# SW102_nRF51x22.net
KiCad netlist of a schematic drawn in EAGLE
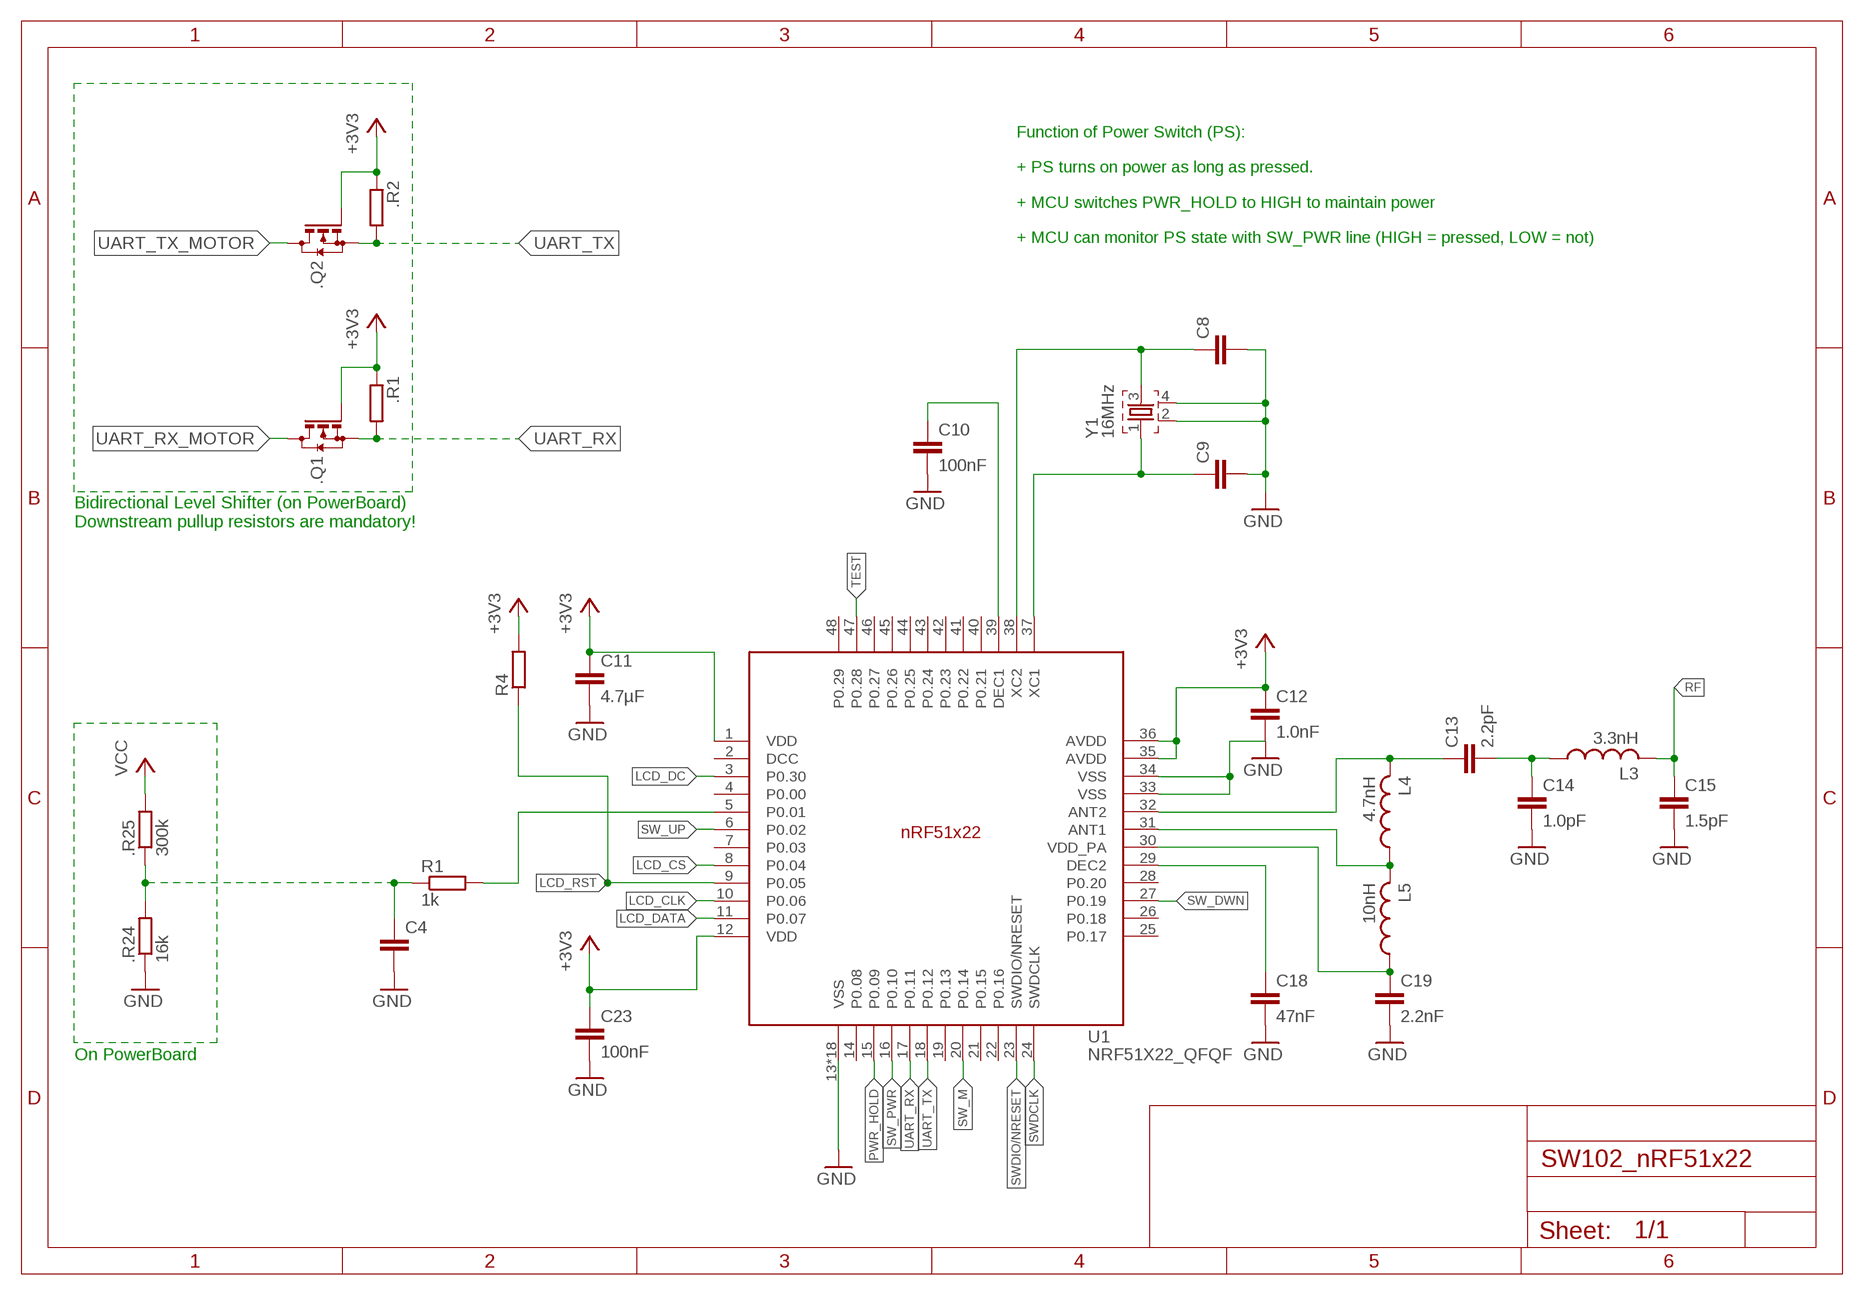
[diagram p0: schematic, sheet 1]

(export (version "E")
  (design (tool "Eeschema 10.0.6"))
  (components
    (comp (ref ".Q1")
      (value "BSS123")
      (footprint "eagle-import:SOT23")
      (libsource (lib "eagle-import") (part "BSS123"))
    )
    (comp (ref ".Q2")
      (value "BSS123")
      (footprint "eagle-import:SOT23")
      (libsource (lib "eagle-import") (part "BSS123"))
    )
    (comp (ref ".R1")
      (value "R-EU_R0603")
      (footprint "eagle-import:R0603")
      (libsource (lib "eagle-import") (part "R-EU_R0603"))
    )
    (comp (ref ".R2")
      (value "R-EU_R0603")
      (footprint "eagle-import:R0603")
      (libsource (lib "eagle-import") (part "R-EU_R0603"))
    )
    (comp (ref ".R24")
      (value "16k")
      (footprint "eagle-import:R0603")
      (libsource (lib "eagle-import") (part "R-EU_R0603"))
    )
    (comp (ref ".R25")
      (value "300k")
      (footprint "eagle-import:R0603")
      (libsource (lib "eagle-import") (part "R-EU_R0603"))
    )
    (comp (ref "C4")
      (value "CAPACITOR_0402_N")
      (footprint "eagle-import:RESC0402_N")
      (libsource (lib "eagle-import") (part "CAPACITOR_0402_N"))
    )
    (comp (ref "C8")
      (value "CAPACITOR_0402_N")
      (footprint "eagle-import:RESC0402_N")
      (libsource (lib "eagle-import") (part "CAPACITOR_0402_N"))
    )
    (comp (ref "C9")
      (value "CAPACITOR_0402_N")
      (footprint "eagle-import:RESC0402_N")
      (libsource (lib "eagle-import") (part "CAPACITOR_0402_N"))
    )
    (comp (ref "C10")
      (value "100nF")
      (footprint "eagle-import:RESC0402_N")
      (libsource (lib "eagle-import") (part "CAPACITOR_0402_N"))
    )
    (comp (ref "C11")
      (value "4.7µF")
      (footprint "eagle-import:RESC0603_N")
      (libsource (lib "eagle-import") (part "CAPACITOR_0603_N"))
    )
    (comp (ref "C12")
      (value "1.0nF")
      (footprint "eagle-import:RESC0402_N")
      (libsource (lib "eagle-import") (part "CAPACITOR_0402_N"))
    )
    (comp (ref "C13")
      (value "2.2pF")
      (footprint "eagle-import:RESC0402_N")
      (libsource (lib "eagle-import") (part "CAPACITOR_0402_N"))
    )
    (comp (ref "C14")
      (value "1.0pF")
      (footprint "eagle-import:RESC0402_N")
      (libsource (lib "eagle-import") (part "CAPACITOR_0402_N"))
    )
    (comp (ref "C15")
      (value "1.5pF")
      (footprint "eagle-import:RESC0402_N")
      (libsource (lib "eagle-import") (part "CAPACITOR_0402_N"))
    )
    (comp (ref "C18")
      (value "47nF")
      (footprint "eagle-import:RESC0402_N")
      (libsource (lib "eagle-import") (part "CAPACITOR_0402_N"))
    )
    (comp (ref "C19")
      (value "2.2nF")
      (footprint "eagle-import:RESC0402_N")
      (libsource (lib "eagle-import") (part "CAPACITOR_0402_N"))
    )
    (comp (ref "C23")
      (value "100nF")
      (footprint "eagle-import:RESC0402_N")
      (libsource (lib "eagle-import") (part "CAPACITOR_0402_N"))
    )
    (comp (ref "L3")
      (value "3.3nH")
      (footprint "eagle-import:RESC0402_N")
      (libsource (lib "eagle-import") (part "INDUCTOR_0402_N"))
    )
    (comp (ref "L4")
      (value "4.7nH")
      (footprint "eagle-import:RESC0402_N")
      (libsource (lib "eagle-import") (part "INDUCTOR_0402_N"))
    )
    (comp (ref "L5")
      (value "10nH")
      (footprint "eagle-import:RESC0402_N")
      (libsource (lib "eagle-import") (part "INDUCTOR_0402_N"))
    )
    (comp (ref "R1")
      (value "1k")
      (footprint "eagle-import:R0603")
      (libsource (lib "eagle-import") (part "R-EU_R0603"))
    )
    (comp (ref "R4")
      (value "R-EU_R0603")
      (footprint "eagle-import:R0603")
      (libsource (lib "eagle-import") (part "R-EU_R0603"))
    )
    (comp (ref "U1")
      (value "NRF51X22_QFQF")
      (footprint "eagle-import:QFN40P600X600X90-48_N")
      (libsource (lib "eagle-import") (part "NRF51X22_QFQF"))
    )
    (comp (ref "Y1")
      (value "16MHz")
      (footprint "eagle-import:BT-XTAL_2016_N")
      (libsource (lib "eagle-import") (part "XTAL_32MHZ"))
    )
  )
  (nets
    (net (code "1") (name "+3V3") (class "Default")
      (node (ref ".Q1") (pin "1") (pinfunction "G_1") (pintype "passive"))
      (node (ref ".Q2") (pin "1") (pinfunction "G_1") (pintype "passive"))
      (node (ref ".R1") (pin "1") (pinfunction "1_1") (pintype "passive"))
      (node (ref ".R2") (pin "1") (pinfunction "1_1") (pintype "passive"))
      (node (ref "C11") (pin "1") (pinfunction "1_1") (pintype "passive"))
      (node (ref "C12") (pin "1") (pinfunction "1_1") (pintype "passive"))
      (node (ref "C23") (pin "1") (pinfunction "1_1") (pintype "passive"))
      (node (ref "R4") (pin "2") (pinfunction "2_2") (pintype "passive"))
      (node (ref "U1") (pin "1") (pinfunction "VDD_1") (pintype "power_in"))
      (node (ref "U1") (pin "12") (pinfunction "VDD_12") (pintype "power_in"))
      (node (ref "U1") (pin "35") (pinfunction "AVDD_35") (pintype "power_in"))
      (node (ref "U1") (pin "36") (pinfunction "AVDD_36") (pintype "power_in"))
    )
    (net (code "2") (name "/DCC") (class "Default")
      (node (ref "U1") (pin "2") (pinfunction "DCC_2") (pintype "power_in"))
    )
    (net (code "3") (name "GND") (class "Default")
      (node (ref ".R24") (pin "1") (pinfunction "1_1") (pintype "passive"))
      (node (ref "C10") (pin "2") (pinfunction "2_2") (pintype "passive"))
      (node (ref "C11") (pin "2") (pinfunction "2_2") (pintype "passive"))
      (node (ref "C12") (pin "2") (pinfunction "2_2") (pintype "passive"))
      (node (ref "C14") (pin "2") (pinfunction "2_2") (pintype "passive"))
      (node (ref "C15") (pin "2") (pinfunction "2_2") (pintype "passive"))
      (node (ref "C18") (pin "2") (pinfunction "2_2") (pintype "passive"))
      (node (ref "C19") (pin "2") (pinfunction "2_2") (pintype "passive"))
      (node (ref "C23") (pin "2") (pinfunction "2_2") (pintype "passive"))
      (node (ref "C4") (pin "2") (pinfunction "2_2") (pintype "passive"))
      (node (ref "C8") (pin "2") (pinfunction "2_2") (pintype "passive"))
      (node (ref "C9") (pin "2") (pinfunction "2_2") (pintype "passive"))
      (node (ref "U1") (pin "13") (pinfunction "VSS_13") (pintype "power_in"))
      (node (ref "U1") (pin "33") (pinfunction "VSS_33") (pintype "power_in"))
      (node (ref "U1") (pin "34") (pinfunction "VSS_34") (pintype "power_in"))
      (node (ref "U1") (pin "PAD") (pinfunction "VSS_PAD") (pintype "power_in"))
      (node (ref "U1") (pin "PAD@VIA01") (pinfunction "VSS_PAD@VIA01") (pintype "power_in"))
      (node (ref "U1") (pin "PAD@VIA02") (pinfunction "VSS_PAD@VIA02") (pintype "power_in"))
      (node (ref "U1") (pin "PAD@VIA03") (pinfunction "VSS_PAD@VIA03") (pintype "power_in"))
      (node (ref "U1") (pin "PAD@VIA04") (pinfunction "VSS_PAD@VIA04") (pintype "power_in"))
      (node (ref "U1") (pin "PAD@VIA05") (pinfunction "VSS_PAD@VIA05") (pintype "power_in"))
      (node (ref "U1") (pin "PAD@VIA06") (pinfunction "VSS_PAD@VIA06") (pintype "power_in"))
      (node (ref "U1") (pin "PAD@VIA07") (pinfunction "VSS_PAD@VIA07") (pintype "power_in"))
      (node (ref "U1") (pin "PAD@VIA08") (pinfunction "VSS_PAD@VIA08") (pintype "power_in"))
      (node (ref "U1") (pin "PAD@VIA09") (pinfunction "VSS_PAD@VIA09") (pintype "power_in"))
      (node (ref "U1") (pin "PAD@VIA10") (pinfunction "VSS_PAD@VIA10") (pintype "power_in"))
      (node (ref "U1") (pin "PAD@VIA11") (pinfunction "VSS_PAD@VIA11") (pintype "power_in"))
      (node (ref "U1") (pin "PAD@VIA12") (pinfunction "VSS_PAD@VIA12") (pintype "power_in"))
      (node (ref "U1") (pin "PAD@VIA13") (pinfunction "VSS_PAD@VIA13") (pintype "power_in"))
      (node (ref "U1") (pin "PAD@VIA14") (pinfunction "VSS_PAD@VIA14") (pintype "power_in"))
      (node (ref "U1") (pin "PAD@VIA15") (pinfunction "VSS_PAD@VIA15") (pintype "power_in"))
      (node (ref "U1") (pin "PAD@VIA16") (pinfunction "VSS_PAD@VIA16") (pintype "power_in"))
      (node (ref "Y1") (pin "2") (pinfunction "2_2") (pintype "passive"))
      (node (ref "Y1") (pin "4") (pinfunction "4_4") (pintype "passive"))
    )
    (net (code "4") (name "LCD_CLK") (class "Default")
      (node (ref "U1") (pin "10") (pinfunction "P0.06_10") (pintype "bidirectional"))
    )
    (net (code "5") (name "LCD_CS") (class "Default")
      (node (ref "U1") (pin "8") (pinfunction "P0.04_8") (pintype "bidirectional"))
    )
    (net (code "6") (name "LCD_DATA") (class "Default")
      (node (ref "U1") (pin "11") (pinfunction "P0.07_11") (pintype "bidirectional"))
    )
    (net (code "7") (name "LCD_DC") (class "Default")
      (node (ref "U1") (pin "3") (pinfunction "P0.30_3") (pintype "bidirectional"))
    )
    (net (code "8") (name "LCD_RST") (class "Default")
      (node (ref "R4") (pin "1") (pinfunction "1_1") (pintype "passive"))
      (node (ref "U1") (pin "9") (pinfunction "P0.05_9") (pintype "bidirectional"))
    )
    (net (code "9") (name "Net-(.R24-Pad2)") (class "Default")
      (node (ref ".R24") (pin "2") (pinfunction "2_2") (pintype "passive"))
      (node (ref ".R25") (pin "1") (pinfunction "1_1") (pintype "passive"))
      (node (ref "C4") (pin "1") (pinfunction "1_1") (pintype "passive"))
      (node (ref "R1") (pin "1") (pinfunction "1_1") (pintype "passive"))
    )
    (net (code "10") (name "Net-(C13-Pad2)") (class "Default")
      (node (ref "C13") (pin "2") (pinfunction "2_2") (pintype "passive"))
      (node (ref "C14") (pin "1") (pinfunction "1_1") (pintype "passive"))
      (node (ref "L3") (pin "1") (pinfunction "1_1") (pintype "passive"))
    )
    (net (code "11") (name "Net-(U1-ANT1)") (class "Default")
      (node (ref "L4") (pin "1") (pinfunction "1_1") (pintype "passive"))
      (node (ref "L5") (pin "2") (pinfunction "2_2") (pintype "passive"))
      (node (ref "U1") (pin "31") (pinfunction "ANT1_31") (pintype "bidirectional"))
    )
    (net (code "12") (name "Net-(U1-ANT2)") (class "Default")
      (node (ref "C13") (pin "1") (pinfunction "1_1") (pintype "passive"))
      (node (ref "L4") (pin "2") (pinfunction "2_2") (pintype "passive"))
      (node (ref "U1") (pin "32") (pinfunction "ANT2_32") (pintype "bidirectional"))
    )
    (net (code "13") (name "Net-(U1-DEC1)") (class "Default")
      (node (ref "C10") (pin "1") (pinfunction "1_1") (pintype "passive"))
      (node (ref "U1") (pin "39") (pinfunction "DEC1_39") (pintype "power_in"))
    )
    (net (code "14") (name "Net-(U1-DEC2)") (class "Default")
      (node (ref "C18") (pin "1") (pinfunction "1_1") (pintype "passive"))
      (node (ref "U1") (pin "29") (pinfunction "DEC2_29") (pintype "power_in"))
    )
    (net (code "15") (name "Net-(U1-P0.01)") (class "Default")
      (node (ref "R1") (pin "2") (pinfunction "2_2") (pintype "passive"))
      (node (ref "U1") (pin "5") (pinfunction "P0.01_5") (pintype "bidirectional"))
    )
    (net (code "16") (name "Net-(U1-VDD_PA)") (class "Default")
      (node (ref "C19") (pin "1") (pinfunction "1_1") (pintype "passive"))
      (node (ref "L5") (pin "1") (pinfunction "1_1") (pintype "passive"))
      (node (ref "U1") (pin "30") (pinfunction "VDD_PA_30") (pintype "power_in"))
    )
    (net (code "17") (name "Net-(U1-XC1)") (class "Default")
      (node (ref "C9") (pin "1") (pinfunction "1_1") (pintype "passive"))
      (node (ref "U1") (pin "37") (pinfunction "XC1_37") (pintype "bidirectional"))
      (node (ref "Y1") (pin "1") (pinfunction "1_1") (pintype "passive"))
    )
    (net (code "18") (name "Net-(U1-XC2)") (class "Default")
      (node (ref "C8") (pin "1") (pinfunction "1_1") (pintype "passive"))
      (node (ref "U1") (pin "38") (pinfunction "XC2_38") (pintype "bidirectional"))
      (node (ref "Y1") (pin "3") (pinfunction "3_3") (pintype "passive"))
    )
    (net (code "19") (name "PWR_HOLD") (class "Default")
      (node (ref "U1") (pin "15") (pinfunction "P0.09_15") (pintype "bidirectional"))
    )
    (net (code "20") (name "RF") (class "Default")
      (node (ref "C15") (pin "1") (pinfunction "1_1") (pintype "passive"))
      (node (ref "L3") (pin "2") (pinfunction "2_2") (pintype "passive"))
    )
    (net (code "21") (name "SWDCLK") (class "Default")
      (node (ref "U1") (pin "24") (pinfunction "SWDCLK_24") (pintype "input"))
    )
    (net (code "22") (name "SWDIO{slash}NRESET") (class "Default")
      (node (ref "U1") (pin "23") (pinfunction "SWDIO/NRESET_23") (pintype "bidirectional"))
    )
    (net (code "23") (name "SW_DWN") (class "Default")
      (node (ref "U1") (pin "27") (pinfunction "P0.19_27") (pintype "bidirectional"))
    )
    (net (code "24") (name "SW_M") (class "Default")
      (node (ref "U1") (pin "20") (pinfunction "P0.14_20") (pintype "bidirectional"))
    )
    (net (code "25") (name "SW_PWR") (class "Default")
      (node (ref "U1") (pin "16") (pinfunction "P0.10_16") (pintype "bidirectional"))
    )
    (net (code "26") (name "SW_UP") (class "Default")
      (node (ref "U1") (pin "6") (pinfunction "P0.02_6") (pintype "bidirectional"))
    )
    (net (code "27") (name "TEST") (class "Default")
      (node (ref "U1") (pin "47") (pinfunction "P0.28_47") (pintype "bidirectional"))
    )
    (net (code "28") (name "UART_RX") (class "Default")
      (node (ref ".Q1") (pin "2") (pinfunction "S_2") (pintype "passive"))
      (node (ref ".R1") (pin "2") (pinfunction "2_2") (pintype "passive"))
      (node (ref "U1") (pin "17") (pinfunction "P0.11_17") (pintype "bidirectional"))
    )
    (net (code "29") (name "UART_RX_MOTOR") (class "Default")
      (node (ref ".Q1") (pin "3") (pinfunction "D_3") (pintype "passive"))
    )
    (net (code "30") (name "UART_TX") (class "Default")
      (node (ref ".Q2") (pin "2") (pinfunction "S_2") (pintype "passive"))
      (node (ref ".R2") (pin "2") (pinfunction "2_2") (pintype "passive"))
      (node (ref "U1") (pin "18") (pinfunction "P0.12_18") (pintype "bidirectional"))
    )
    (net (code "31") (name "UART_TX_MOTOR") (class "Default")
      (node (ref ".Q2") (pin "3") (pinfunction "D_3") (pintype "passive"))
    )
    (net (code "32") (name "VCC") (class "Default")
      (node (ref ".R25") (pin "2") (pinfunction "2_2") (pintype "passive"))
    )
    (net (code "33") (name "unconnected-(U1-P0.00-Pad4)") (class "Default")
      (node (ref "U1") (pin "4") (pinfunction "P0.00_4") (pintype "bidirectional"))
    )
    (net (code "34") (name "unconnected-(U1-P0.03-Pad7)") (class "Default")
      (node (ref "U1") (pin "7") (pinfunction "P0.03_7") (pintype "bidirectional"))
    )
    (net (code "35") (name "unconnected-(U1-P0.08-Pad14)") (class "Default")
      (node (ref "U1") (pin "14") (pinfunction "P0.08_14") (pintype "bidirectional"))
    )
    (net (code "36") (name "unconnected-(U1-P0.13-Pad19)") (class "Default")
      (node (ref "U1") (pin "19") (pinfunction "P0.13_19") (pintype "bidirectional"))
    )
    (net (code "37") (name "unconnected-(U1-P0.15-Pad21)") (class "Default")
      (node (ref "U1") (pin "21") (pinfunction "P0.15_21") (pintype "bidirectional"))
    )
    (net (code "38") (name "unconnected-(U1-P0.16-Pad22)") (class "Default")
      (node (ref "U1") (pin "22") (pinfunction "P0.16_22") (pintype "bidirectional"))
    )
    (net (code "39") (name "unconnected-(U1-P0.17-Pad25)") (class "Default")
      (node (ref "U1") (pin "25") (pinfunction "P0.17_25") (pintype "bidirectional"))
    )
    (net (code "40") (name "unconnected-(U1-P0.18-Pad26)") (class "Default")
      (node (ref "U1") (pin "26") (pinfunction "P0.18_26") (pintype "bidirectional"))
    )
    (net (code "41") (name "unconnected-(U1-P0.20-Pad28)") (class "Default")
      (node (ref "U1") (pin "28") (pinfunction "P0.20_28") (pintype "bidirectional"))
    )
    (net (code "42") (name "unconnected-(U1-P0.21-Pad40)") (class "Default")
      (node (ref "U1") (pin "40") (pinfunction "P0.21_40") (pintype "bidirectional"))
    )
    (net (code "43") (name "unconnected-(U1-P0.22-Pad41)") (class "Default")
      (node (ref "U1") (pin "41") (pinfunction "P0.22_41") (pintype "bidirectional"))
    )
    (net (code "44") (name "unconnected-(U1-P0.23-Pad42)") (class "Default")
      (node (ref "U1") (pin "42") (pinfunction "P0.23_42") (pintype "bidirectional"))
    )
    (net (code "45") (name "unconnected-(U1-P0.24-Pad43)") (class "Default")
      (node (ref "U1") (pin "43") (pinfunction "P0.24_43") (pintype "bidirectional"))
    )
    (net (code "46") (name "unconnected-(U1-P0.25-Pad44)") (class "Default")
      (node (ref "U1") (pin "44") (pinfunction "P0.25_44") (pintype "bidirectional"))
    )
    (net (code "47") (name "unconnected-(U1-P0.26-Pad45)") (class "Default")
      (node (ref "U1") (pin "45") (pinfunction "P0.26_45") (pintype "bidirectional"))
    )
    (net (code "48") (name "unconnected-(U1-P0.27-Pad46)") (class "Default")
      (node (ref "U1") (pin "46") (pinfunction "P0.27_46") (pintype "bidirectional"))
    )
    (net (code "49") (name "unconnected-(U1-P0.29-Pad48)") (class "Default")
      (node (ref "U1") (pin "48") (pinfunction "P0.29_48") (pintype "bidirectional"))
    )
  )
)
